# GPS_L80.net
KiCad netlist of a schematic drawn in Altium Designer
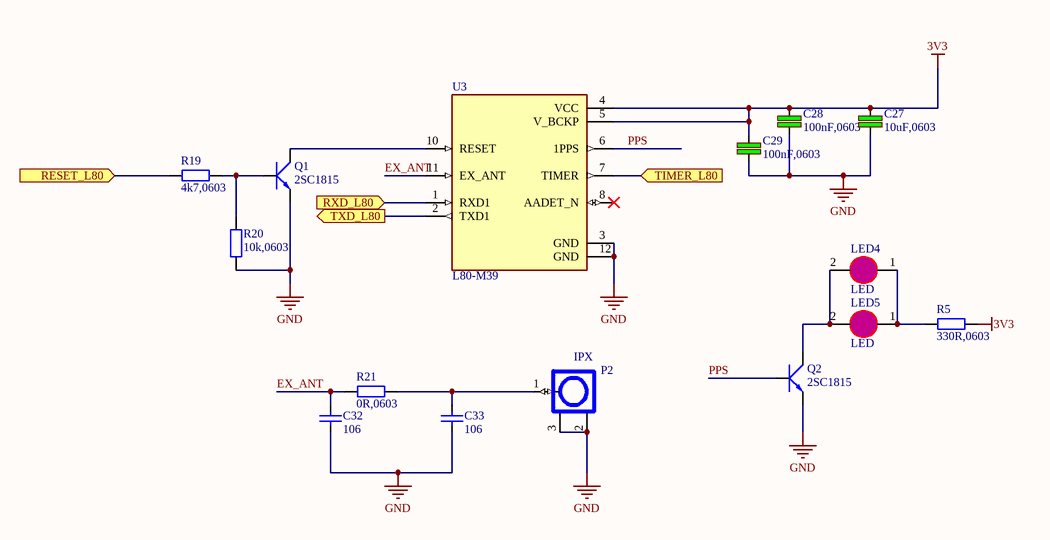
[diagram p0: GPS_L80.SchDoc]

(export (version "E")
  (design (tool "Eeschema 10.0.6"))
  (components
    (comp (ref "C27")
      (value "10uF,0603")
      (footprint "CAP_0603")
      (description "4.7µF ±10% 35V Ceramic Capacitor X5R 0805 (2012 Metric)")
      (fields
        (field (name "MANUFACTURER") "Samsung Electro-Mechanics")
        (field (name "PART NUMBER") "CL21A475KLCLQNC")
      )
      (libsource (lib "Anh_Trung") (part "C"))
    )
    (comp (ref "C28")
      (value "100nF,0603")
      (footprint "CAP_0603")
      (description "4.7µF ±10% 35V Ceramic Capacitor X5R 0805 (2012 Metric)")
      (fields
        (field (name "MANUFACTURER") "Samsung Electro-Mechanics")
        (field (name "PART NUMBER") "CL21A475KLCLQNC")
      )
      (libsource (lib "Anh_Trung") (part "C"))
    )
    (comp (ref "C29")
      (value "100nF,0603")
      (footprint "CAP_0603")
      (description "4.7µF ±10% 35V Ceramic Capacitor X5R 0805 (2012 Metric)")
      (fields
        (field (name "MANUFACTURER") "Samsung Electro-Mechanics")
        (field (name "PART NUMBER") "CL21A475KLCLQNC")
      )
      (libsource (lib "Anh_Trung") (part "C"))
    )
    (comp (ref "C32")
      (value "106")
      (footprint "CAP_0603")
      (description "Capacitor")
      (fields (field (name "PUBLISHER") "Altium Limited"))
      (libsource (lib "My Library") (part "CapSMD"))
    )
    (comp (ref "C33")
      (value "106")
      (footprint "CAP_0603")
      (description "Capacitor")
      (fields (field (name "PUBLISHER") "Altium Limited"))
      (libsource (lib "My Library") (part "CapSMD"))
    )
    (comp (ref "LED4")
      (value "LED")
      (footprint "LED0805")
      (description "LED SMD 0805")
      (libsource (lib "My Library 2") (part "LED0805"))
    )
    (comp (ref "LED5")
      (value "LED")
      (footprint "LED0805")
      (description "LED SMD 0805")
      (libsource (lib "My Library 2") (part "LED0805"))
    )
    (comp (ref "P2")
      (value "IPX")
      (footprint "IPXS")
      (description "Antenna GSM GPS")
      (fields
        (field (name "MANUFACTURER") "TE Connectivity AMP Connectors")
        (field (name "PART NUMBER") "2334884-1")
      )
      (libsource (lib "Anh_Trung") (part "IPXSx66"))
    )
    (comp (ref "Q1")
      (value "2SC1815")
      (footprint "SOT23")
      (description "NPN 600mW, ECB")
      (libsource (lib "My Library 2") (part "2SC1815"))
    )
    (comp (ref "Q2")
      (value "2SC1815")
      (footprint "SOT23-321")
      (description "NPN 600mW, ECB")
      (libsource (lib "My Library 2") (part "2SC1815"))
    )
    (comp (ref "R5")
      (value "330R,0603")
      (footprint "RES-SMD-0603")
      (description "Resistor SMD")
      (fields
        (field (name "MANUFACTURER") "Generic Components")
        (field (name "PUBLISHER") "Altium Hobart Technology Centre")
      )
      (libsource (lib "My Library") (part "Resistor - SMD"))
    )
    (comp (ref "R19")
      (value "4k7,0603")
      (footprint "RES-SMD-0603")
      (description "Resistor SMD")
      (fields
        (field (name "MANUFACTURER") "Generic Components")
        (field (name "PUBLISHER") "Altium Hobart Technology Centre")
      )
      (libsource (lib "My Library") (part "Resistor - SMD"))
    )
    (comp (ref "R20")
      (value "10k,0603")
      (footprint "RES-SMD-0603")
      (description "Resistor SMD")
      (fields
        (field (name "MANUFACTURER") "Generic Components")
        (field (name "PUBLISHER") "Altium Hobart Technology Centre")
      )
      (libsource (lib "My Library") (part "Resistor - SMD"))
    )
    (comp (ref "R21")
      (value "0R,0603")
      (footprint "RES-SMD-0603")
      (description "Resistor SMD")
      (fields
        (field (name "MANUFACTURER") "Generic Components")
        (field (name "PUBLISHER") "Altium Hobart Technology Centre")
      )
      (libsource (lib "My Library") (part "Resistor - SMD"))
    )
    (comp (ref "U3")
      (value "L80-M39")
      (footprint "XCVR_L80-M39")
      (fields (field (name "MF") "Quectel"))
      (libsource (lib "L80-M39") (part "L80-M39"))
    )
  )
  (nets
    (net (code "1") (name "/EX_ANT") (class "Default")
      (node (ref "C32") (pin "2") (pinfunction "2_2") (pintype "passive"))
      (node (ref "R21") (pin "2") (pinfunction "2_2") (pintype "passive"))
      (node (ref "U3") (pin "11") (pinfunction "EX_ANT_11") (pintype "input"))
    )
    (net (code "2") (name "/PPS") (class "Default")
      (node (ref "Q2") (pin "3") (pinfunction "B_3") (pintype "passive"))
      (node (ref "U3") (pin "6") (pinfunction "1PPS_6") (pintype "output"))
    )
    (net (code "3") (name "/RESET_L80") (class "Default")
      (node (ref "R19") (pin "2") (pinfunction "2_2") (pintype "passive"))
    )
    (net (code "4") (name "/RXD_L80") (class "Default")
      (node (ref "U3") (pin "1") (pinfunction "RXD1_1") (pintype "input"))
    )
    (net (code "5") (name "/TIMER_L80") (class "Default")
      (node (ref "U3") (pin "7") (pinfunction "TIMER_7") (pintype "output"))
    )
    (net (code "6") (name "/TXD_L80") (class "Default")
      (node (ref "U3") (pin "2") (pinfunction "TXD1_2") (pintype "output"))
    )
    (net (code "7") (name "3V3") (class "Default")
      (node (ref "C27") (pin "2") (pinfunction "2_2") (pintype "passive"))
      (node (ref "C28") (pin "2") (pinfunction "2_2") (pintype "passive"))
      (node (ref "C29") (pin "2") (pinfunction "2_2") (pintype "passive"))
      (node (ref "R5") (pin "1") (pinfunction "1_1") (pintype "passive"))
      (node (ref "U3") (pin "4") (pinfunction "VCC_4") (pintype "power_in"))
      (node (ref "U3") (pin "5") (pinfunction "V_BCKP_5") (pintype "power_in"))
    )
    (net (code "8") (name "GND") (class "Default")
      (node (ref "C27") (pin "1") (pinfunction "1_1") (pintype "passive"))
      (node (ref "C28") (pin "1") (pinfunction "1_1") (pintype "passive"))
      (node (ref "C29") (pin "1") (pinfunction "1_1") (pintype "passive"))
      (node (ref "C32") (pin "1") (pinfunction "1_1") (pintype "passive"))
      (node (ref "C33") (pin "1") (pinfunction "1_1") (pintype "passive"))
      (node (ref "P2") (pin "2") (pintype "passive"))
      (node (ref "P2") (pin "3") (pintype "passive"))
      (node (ref "Q1") (pin "1") (pinfunction "E_1") (pintype "passive"))
      (node (ref "Q2") (pin "1") (pinfunction "E_1") (pintype "passive"))
      (node (ref "R20") (pin "1") (pinfunction "1_1") (pintype "passive"))
      (node (ref "U3") (pin "12") (pinfunction "GND_12") (pintype "power_in"))
      (node (ref "U3") (pin "3") (pinfunction "GND_3") (pintype "power_in"))
    )
    (net (code "9") (name "Net-(C33-Pad2)") (class "Default")
      (node (ref "C33") (pin "2") (pinfunction "2_2") (pintype "passive"))
      (node (ref "P2") (pin "1") (pintype "bidirectional"))
      (node (ref "R21") (pin "1") (pinfunction "1_1") (pintype "passive"))
    )
    (net (code "10") (name "Net-(LED4-A)") (class "Default")
      (node (ref "LED4") (pin "1") (pinfunction "A_1") (pintype "passive"))
      (node (ref "LED5") (pin "1") (pinfunction "A_1") (pintype "passive"))
      (node (ref "R5") (pin "2") (pinfunction "2_2") (pintype "passive"))
    )
    (net (code "11") (name "Net-(LED4-K)") (class "Default")
      (node (ref "LED4") (pin "2") (pinfunction "K_2") (pintype "passive"))
      (node (ref "LED5") (pin "2") (pinfunction "K_2") (pintype "passive"))
      (node (ref "Q2") (pin "2") (pinfunction "C_2") (pintype "passive"))
    )
    (net (code "12") (name "Net-(Q1-B)") (class "Default")
      (node (ref "Q1") (pin "3") (pinfunction "B_3") (pintype "passive"))
      (node (ref "R19") (pin "1") (pinfunction "1_1") (pintype "passive"))
      (node (ref "R20") (pin "2") (pinfunction "2_2") (pintype "passive"))
    )
    (net (code "13") (name "Net-(Q1-C)") (class "Default")
      (node (ref "Q1") (pin "2") (pinfunction "C_2") (pintype "passive"))
      (node (ref "U3") (pin "10") (pinfunction "RESET_10") (pintype "input"))
    )
    (net (code "14") (name "unconnected-(U3-AADET_N-Pad8)") (class "Default")
      (node (ref "U3") (pin "8") (pinfunction "AADET_N_8") (pintype "bidirectional+no_connect"))
    )
  )
)
